# S7G7_footprint_simplified_w_ethernet_v1p.net
KiCad netlist of a schematic drawn in EAGLE
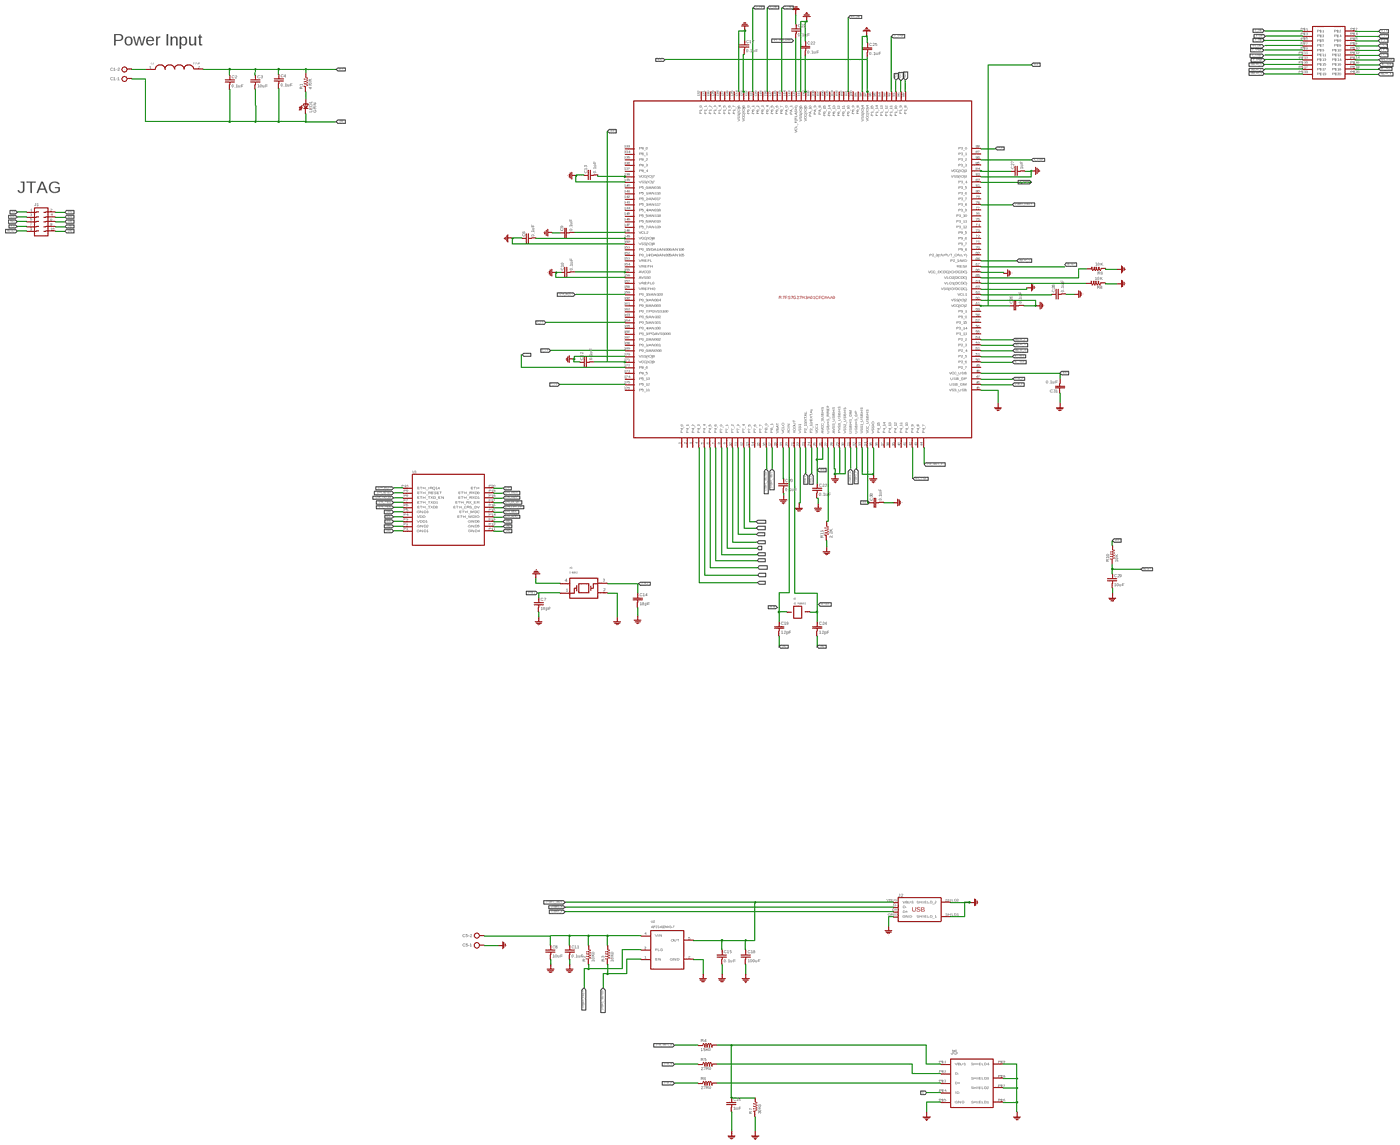
[diagram p0: schematic, sheet 1, overview]
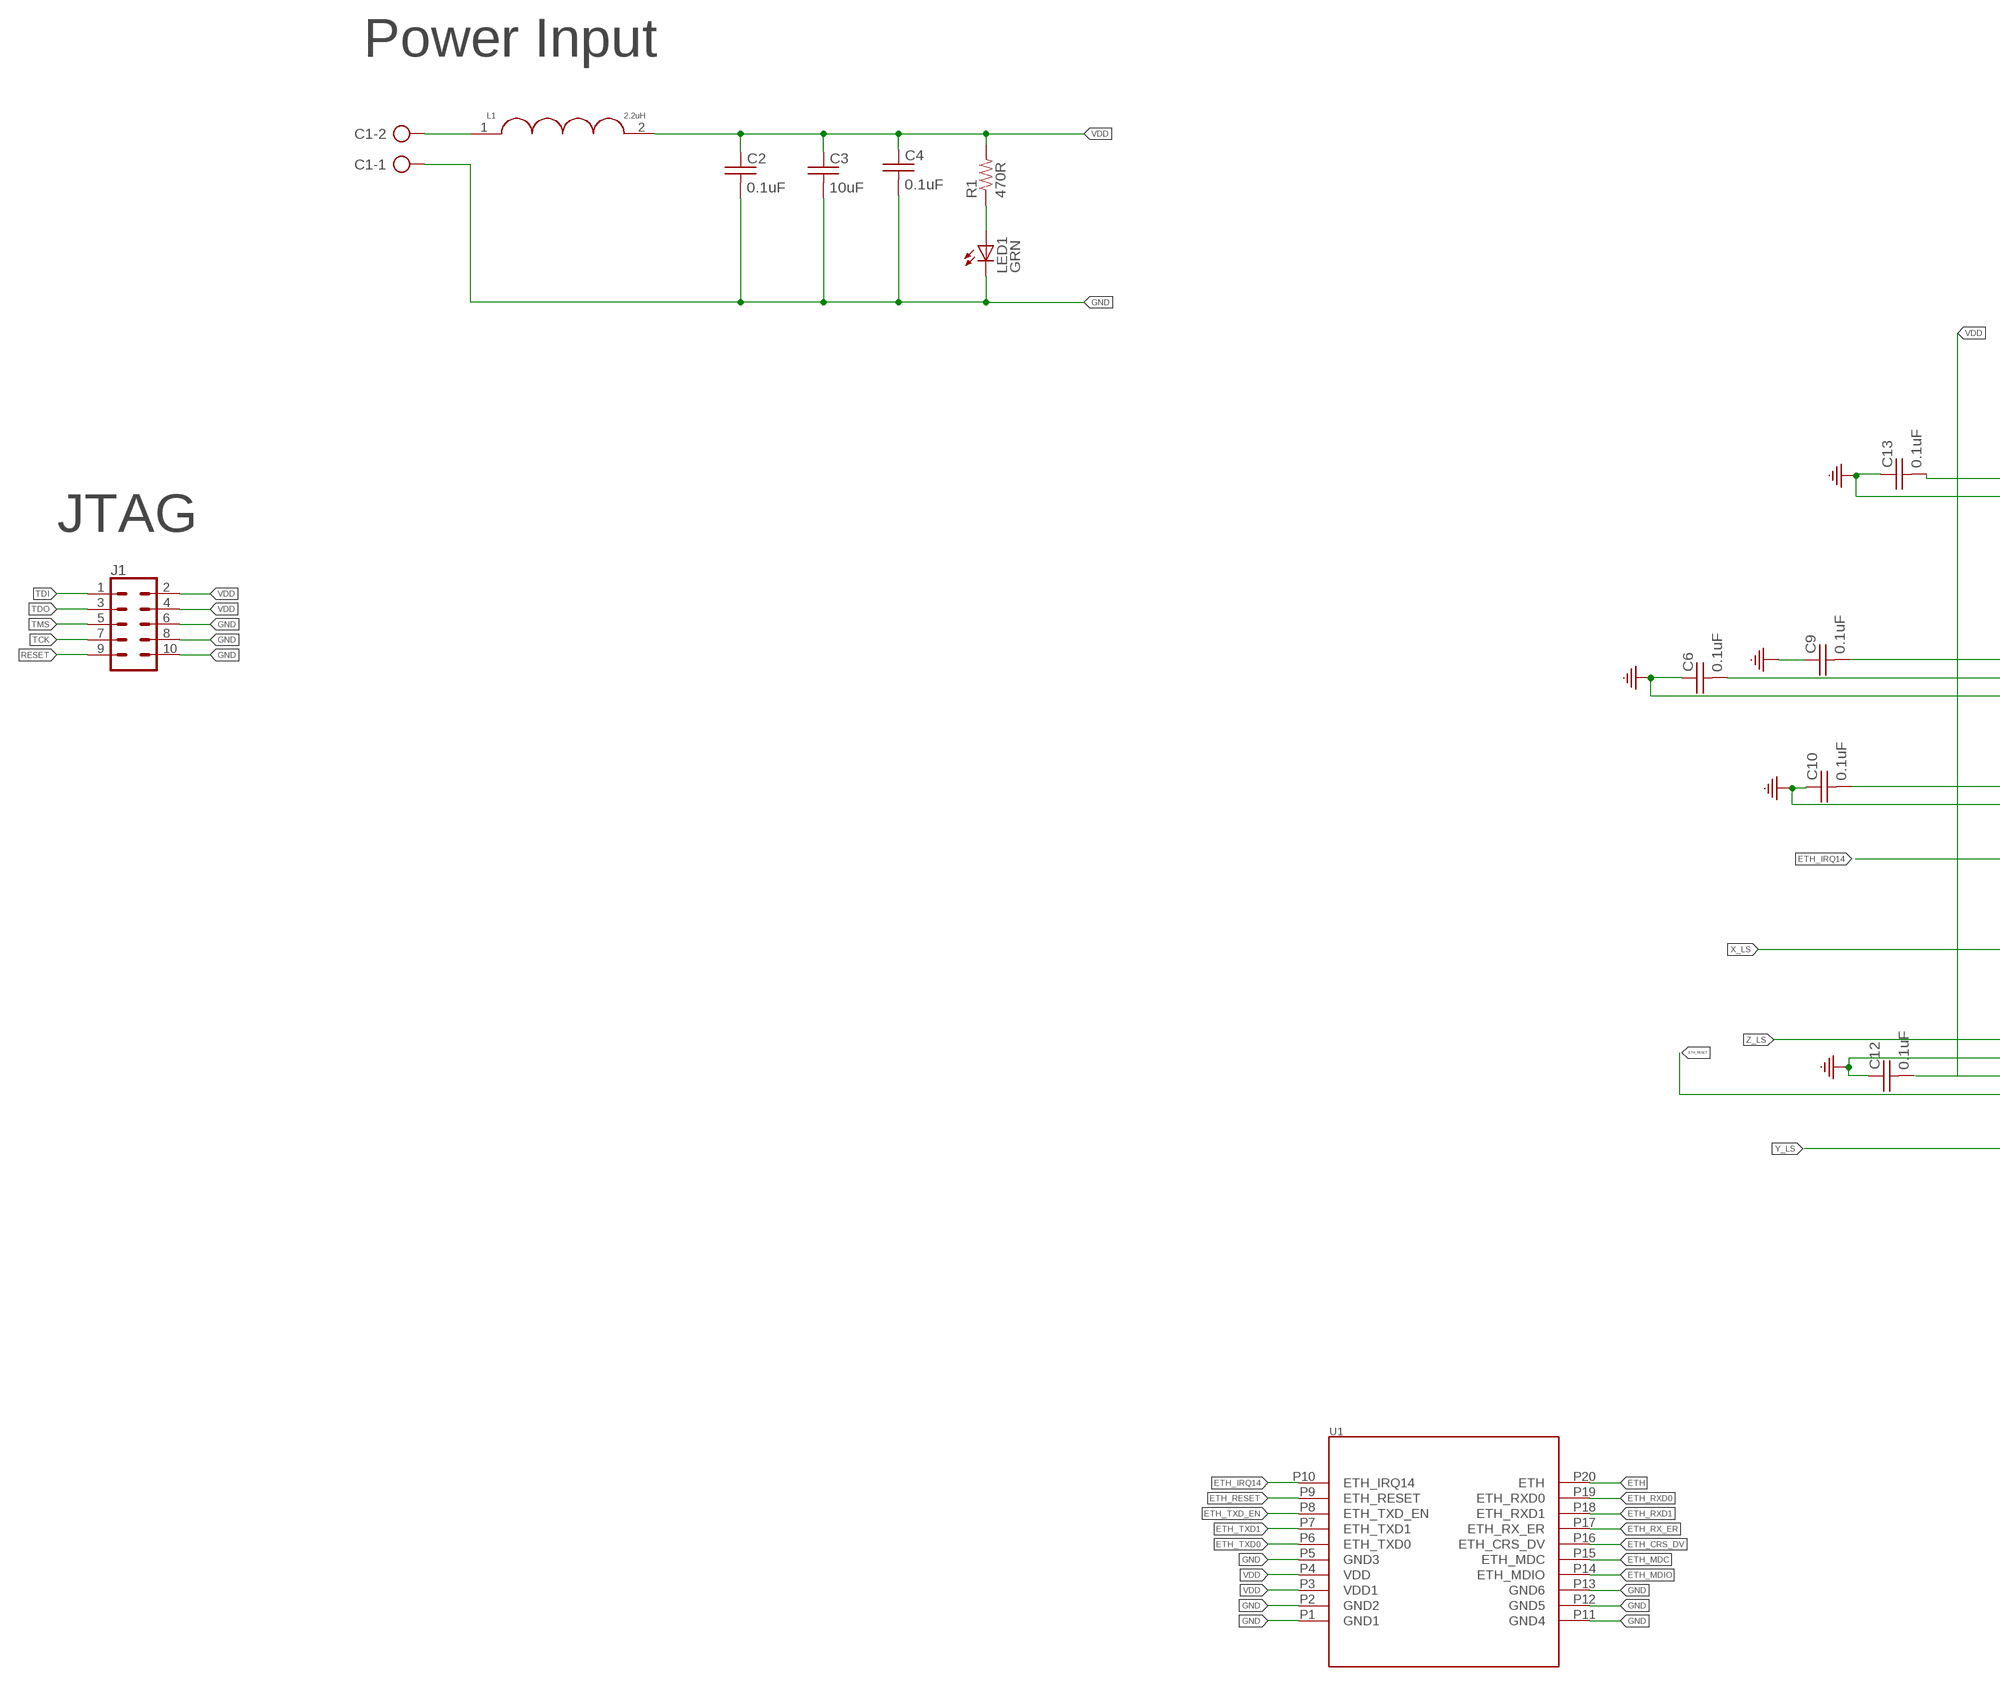
[diagram p1: schematic, sheet 1, part 1 of 4]
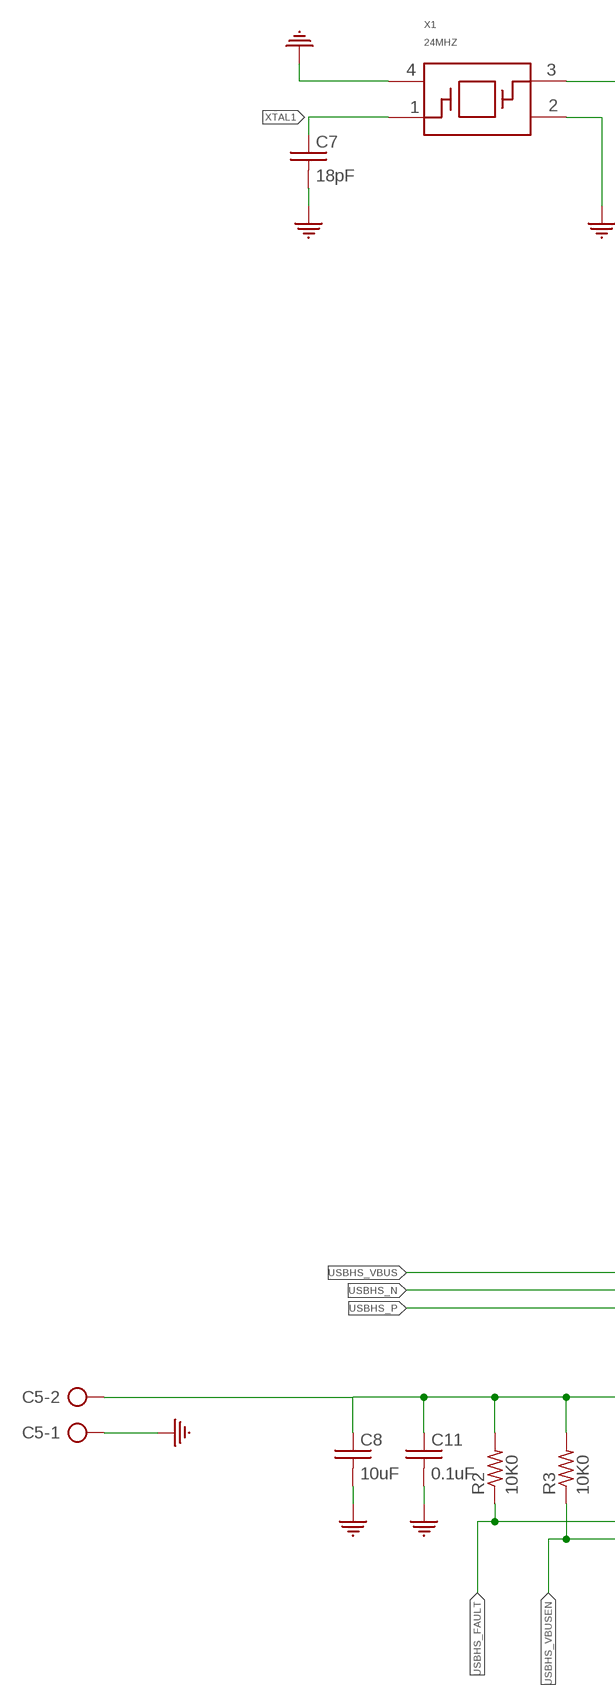
[diagram p2: schematic, sheet 1, part 2 of 4]
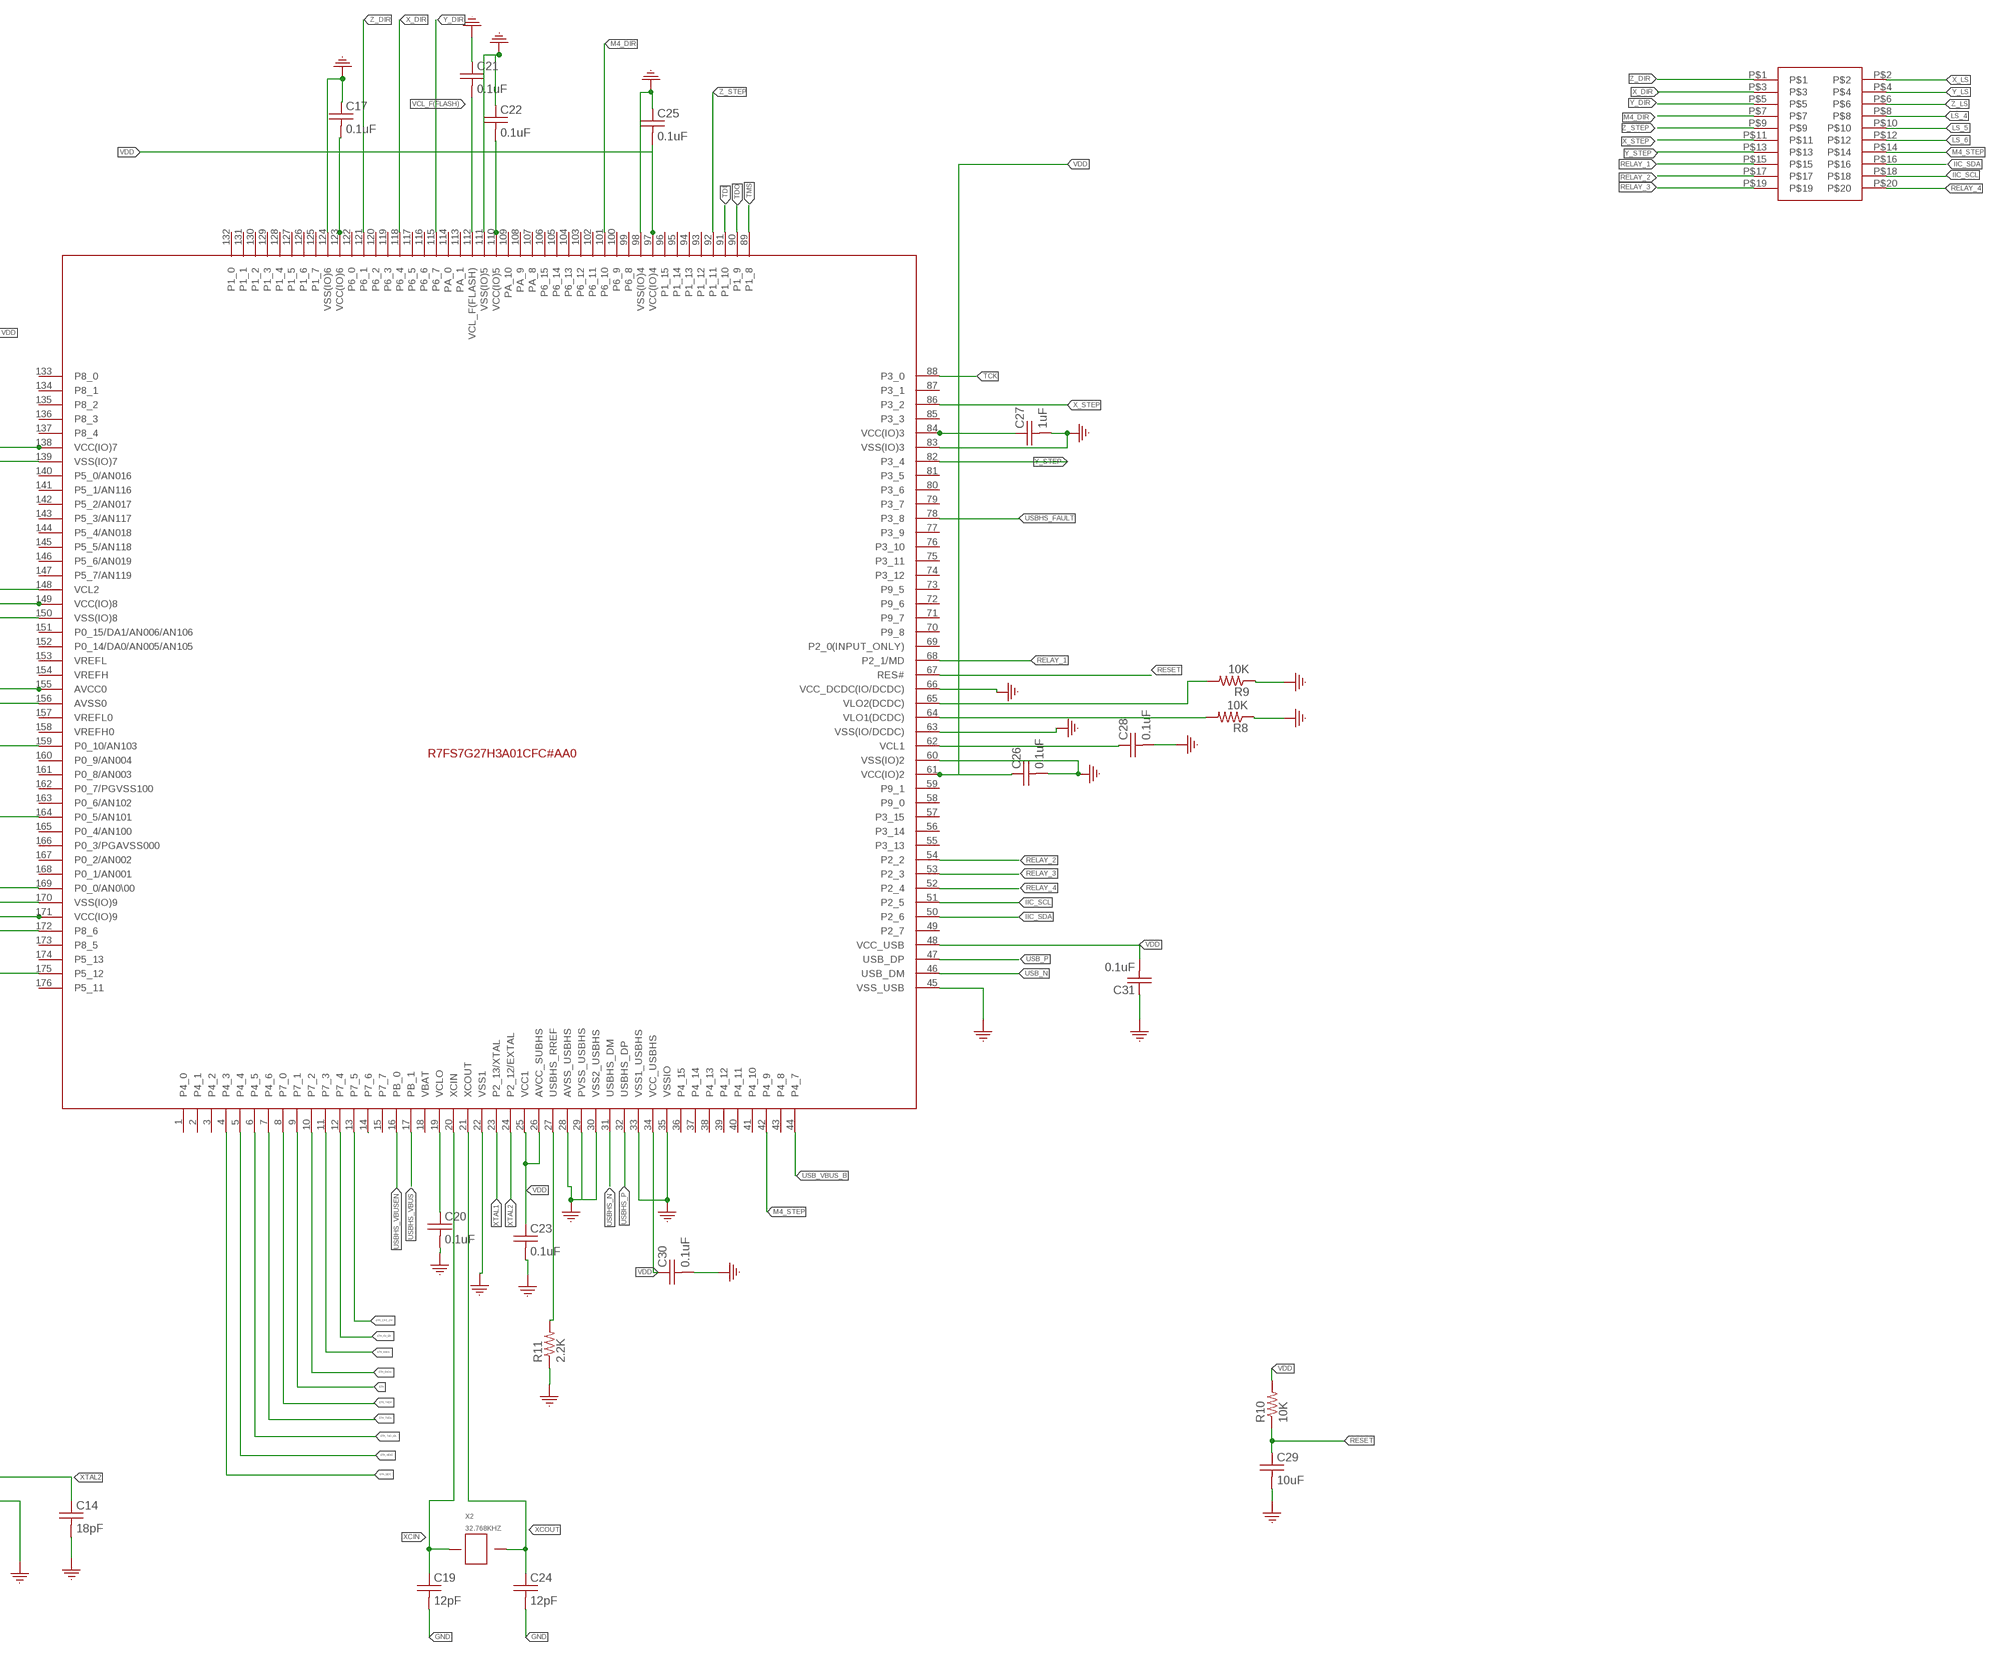
[diagram p3: schematic, sheet 1, part 3 of 4]
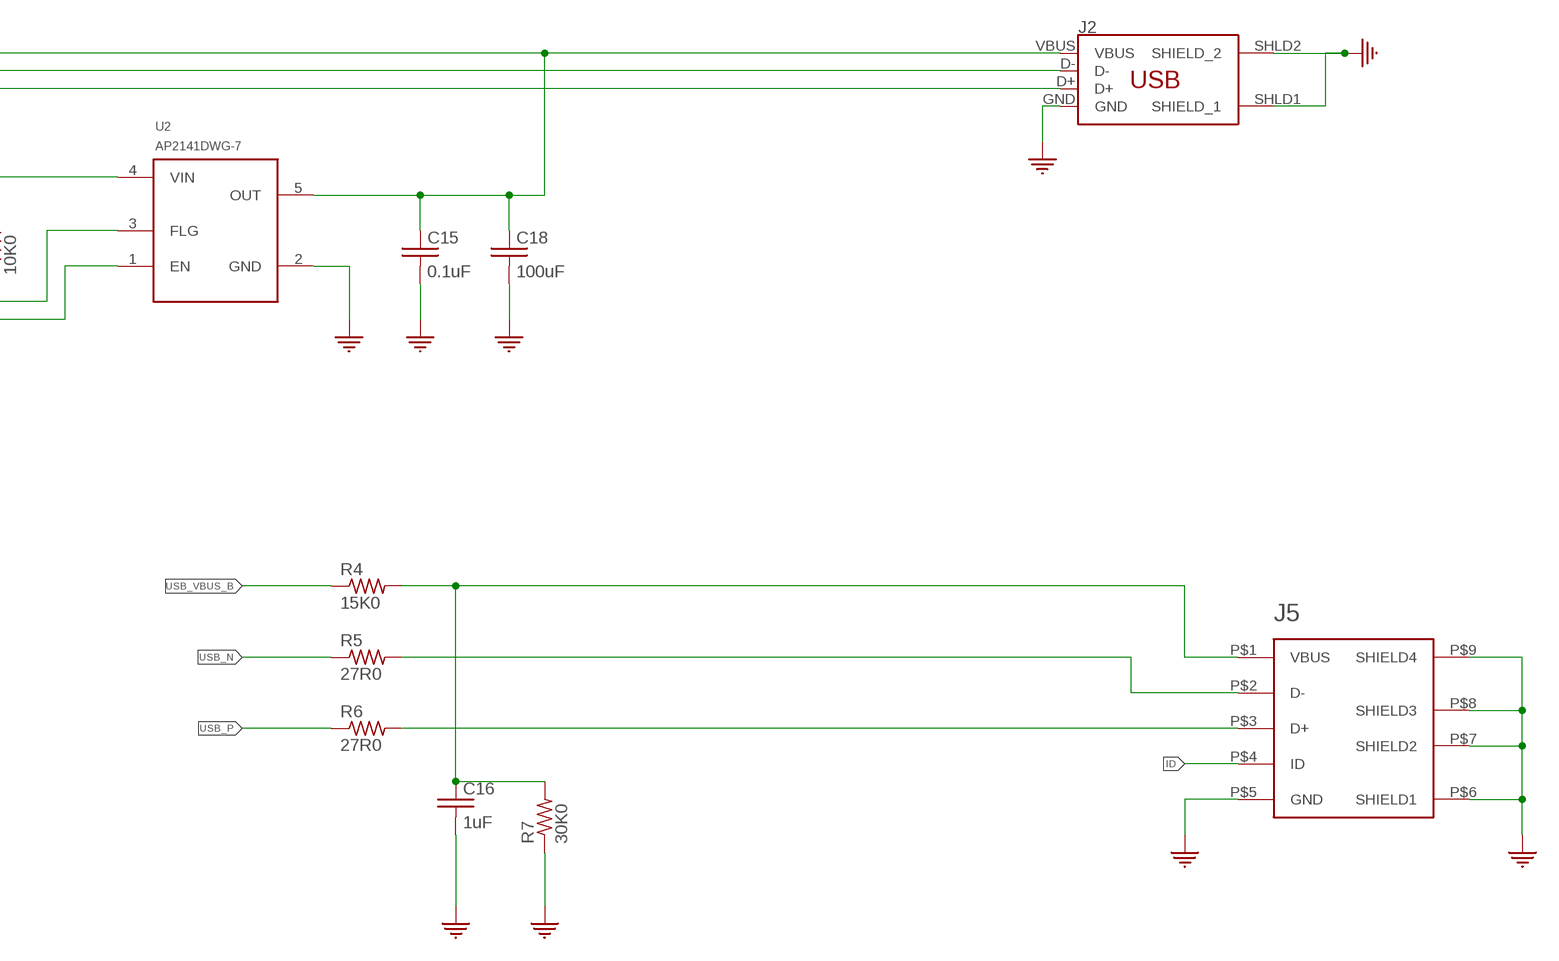
[diagram p4: schematic, sheet 1, part 4 of 4]

(export (version "E")
  (design (tool "Eeschema 10.0.6"))
  (components
    (comp (ref "C1")
      (value "AK300/2")
      (footprint "eagle-import:AK300_2")
      (libsource (lib "eagle-import") (part "AK300/2"))
    )
    (comp (ref "C2")
      (value "0.1uF")
      (footprint "eagle-import:0402")
      (libsource (lib "eagle-import") (part "C_0402"))
    )
    (comp (ref "C3")
      (value "10uF")
      (footprint "eagle-import:0402")
      (libsource (lib "eagle-import") (part "C_0402"))
    )
    (comp (ref "C4")
      (value "0.1uF")
      (footprint "eagle-import:0402")
      (libsource (lib "eagle-import") (part "C_0402"))
    )
    (comp (ref "C5")
      (value "AK300/2")
      (footprint "eagle-import:AK300_2")
      (libsource (lib "eagle-import") (part "AK300/2"))
    )
    (comp (ref "C6")
      (value "0.1uF")
      (footprint "eagle-import:0402")
      (libsource (lib "eagle-import") (part "C_0402"))
    )
    (comp (ref "C7")
      (value "18pF")
      (footprint "eagle-import:0402")
      (libsource (lib "eagle-import") (part "C_0402"))
    )
    (comp (ref "C8")
      (value "10uF")
      (footprint "eagle-import:0402")
      (libsource (lib "eagle-import") (part "C_0402"))
    )
    (comp (ref "C9")
      (value "0.1uF")
      (footprint "eagle-import:0402")
      (libsource (lib "eagle-import") (part "C_0402"))
    )
    (comp (ref "C10")
      (value "0.1uF")
      (footprint "eagle-import:0402")
      (libsource (lib "eagle-import") (part "C_0402"))
    )
    (comp (ref "C11")
      (value "0.1uF")
      (footprint "eagle-import:0402")
      (libsource (lib "eagle-import") (part "C_0402"))
    )
    (comp (ref "C12")
      (value "0.1uF")
      (footprint "eagle-import:0402")
      (libsource (lib "eagle-import") (part "C_0402"))
    )
    (comp (ref "C13")
      (value "0.1uF")
      (footprint "eagle-import:0402")
      (libsource (lib "eagle-import") (part "C_0402"))
    )
    (comp (ref "C14")
      (value "18pF")
      (footprint "eagle-import:0402")
      (libsource (lib "eagle-import") (part "C_0402"))
    )
    (comp (ref "C15")
      (value "0.1uF")
      (footprint "eagle-import:0402")
      (libsource (lib "eagle-import") (part "C_0402"))
    )
    (comp (ref "C16")
      (value "1uF")
      (footprint "eagle-import:0402")
      (libsource (lib "eagle-import") (part "C_0402"))
    )
    (comp (ref "C17")
      (value "0.1uF")
      (footprint "eagle-import:0402")
      (libsource (lib "eagle-import") (part "C_0402"))
    )
    (comp (ref "C18")
      (value "100uF")
      (footprint "eagle-import:C2917")
      (libsource (lib "eagle-import") (part "C_2917"))
    )
    (comp (ref "C19")
      (value "12pF")
      (footprint "eagle-import:0402")
      (libsource (lib "eagle-import") (part "C_0402"))
    )
    (comp (ref "C20")
      (value "0.1uF")
      (footprint "eagle-import:0402")
      (libsource (lib "eagle-import") (part "C_0402"))
    )
    (comp (ref "C21")
      (value "0.1uF")
      (footprint "eagle-import:0402")
      (libsource (lib "eagle-import") (part "C_0402"))
    )
    (comp (ref "C22")
      (value "0.1uF")
      (footprint "eagle-import:0402")
      (libsource (lib "eagle-import") (part "C_0402"))
    )
    (comp (ref "C23")
      (value "0.1uF")
      (footprint "eagle-import:0402")
      (libsource (lib "eagle-import") (part "C_0402"))
    )
    (comp (ref "C24")
      (value "12pF")
      (footprint "eagle-import:0402")
      (libsource (lib "eagle-import") (part "C_0402"))
    )
    (comp (ref "C25")
      (value "0.1uF")
      (footprint "eagle-import:0402")
      (libsource (lib "eagle-import") (part "C_0402"))
    )
    (comp (ref "C26")
      (value "0.1uF")
      (footprint "eagle-import:0402")
      (libsource (lib "eagle-import") (part "C_0402"))
    )
    (comp (ref "C27")
      (value "1uF")
      (footprint "eagle-import:0402")
      (libsource (lib "eagle-import") (part "C_0402"))
    )
    (comp (ref "C28")
      (value "0.1uF")
      (footprint "eagle-import:0402")
      (libsource (lib "eagle-import") (part "C_0402"))
    )
    (comp (ref "C29")
      (value "10uF")
      (footprint "eagle-import:0402")
      (libsource (lib "eagle-import") (part "C_0402"))
    )
    (comp (ref "C30")
      (value "0.1uF")
      (footprint "eagle-import:0402")
      (libsource (lib "eagle-import") (part "C_0402"))
    )
    (comp (ref "C31")
      (value "0.1uF")
      (footprint "eagle-import:0402")
      (libsource (lib "eagle-import") (part "C_0402"))
    )
    (comp (ref "J1")
      (value "CONN_05X2PTH")
      (footprint "eagle-import:2X5")
      (libsource (lib "eagle-import") (part "CONN_05X2PTH"))
    )
    (comp (ref "J2")
      (value "USB_A")
      (footprint "eagle-import:USB_A_SMT")
      (libsource (lib "eagle-import") (part "USB_A"))
    )
    (comp (ref "J4")
      (value "2_X_10_HEADER_GENERIC")
      (footprint "eagle-import:2_X_10_.1_INCH")
      (libsource (lib "eagle-import") (part "2_X_10_HEADER_GENERIC"))
    )
    (comp (ref "J5")
      (value "USB_MICRO-B")
      (footprint "eagle-import:USB_MICRO-B")
      (libsource (lib "eagle-import") (part "USB_MICRO-B"))
    )
    (comp (ref "L1")
      (value "2.2uH")
      (footprint "eagle-import:1008_(2520_METRIC)")
      (libsource (lib "eagle-import") (part "INDUCTOR_1008_2.2_MH_1.3A"))
    )
    (comp (ref "LED1")
      (value "LED_0805_GREEN")
      (footprint "eagle-import:LED_0805_GREEN")
      (libsource (lib "eagle-import") (part "LED_0805_GREEN"))
    )
    (comp (ref "R1")
      (value "470R")
      (footprint "eagle-import:0402")
      (libsource (lib "eagle-import") (part "R_0402"))
    )
    (comp (ref "R2")
      (value "10K0")
      (footprint "eagle-import:0402")
      (libsource (lib "eagle-import") (part "R_0402"))
    )
    (comp (ref "R3")
      (value "10K0")
      (footprint "eagle-import:0402")
      (libsource (lib "eagle-import") (part "R_0402"))
    )
    (comp (ref "R4")
      (value "15K0")
      (footprint "eagle-import:0402")
      (libsource (lib "eagle-import") (part "R_0402"))
    )
    (comp (ref "R5")
      (value "27R0")
      (footprint "eagle-import:0402")
      (libsource (lib "eagle-import") (part "R_0402"))
    )
    (comp (ref "R6")
      (value "27R0")
      (footprint "eagle-import:0402")
      (libsource (lib "eagle-import") (part "R_0402"))
    )
    (comp (ref "R7")
      (value "30K0")
      (footprint "eagle-import:0402")
      (libsource (lib "eagle-import") (part "R_0402"))
    )
    (comp (ref "R8")
      (value "10K")
      (footprint "eagle-import:0402")
      (libsource (lib "eagle-import") (part "R_0402"))
    )
    (comp (ref "R9")
      (value "10K")
      (footprint "eagle-import:0402")
      (libsource (lib "eagle-import") (part "R_0402"))
    )
    (comp (ref "R10")
      (value "10K")
      (footprint "eagle-import:0402")
      (libsource (lib "eagle-import") (part "R_0402"))
    )
    (comp (ref "R11")
      (value "2.2K")
      (footprint "eagle-import:0402")
      (libsource (lib "eagle-import") (part "R_0402"))
    )
    (comp (ref "U1")
      (value "ETHERNET_HAT")
      (footprint "eagle-import:ETHERNET_HAT")
      (libsource (lib "eagle-import") (part "ETHERNET_HAT"))
    )
    (comp (ref "U2")
      (value "AP2141DWG-5")
      (footprint "eagle-import:SOT-23-5")
      (libsource (lib "eagle-import") (part "AP2141DWG-5"))
    )
    (comp (ref "U5")
      (value "S7G2_X_176")
      (footprint "eagle-import:LQFP176_24X24")
      (libsource (lib "eagle-import") (part "S7G2_X_176"))
    )
    (comp (ref "X1")
      (value "24MHZ")
      (footprint "eagle-import:SMD_3225")
      (libsource (lib "eagle-import") (part "XTAL_24_MHZ"))
    )
    (comp (ref "X2")
      (value "32.768KHZ")
      (footprint "eagle-import:SMD_X_2_PADS")
      (libsource (lib "eagle-import") (part "XTAL_32.768KHZ"))
    )
  )
  (nets
    (net (code "1") (name "ETH") (class "Default")
      (node (ref "U1") (pin "P20") (pinfunction "ETH_P20") (pintype "bidirectional"))
      (node (ref "U5") (pin "9") (pinfunction "P7_1_9") (pintype "bidirectional"))
    )
    (net (code "2") (name "ETH_CRS_DV") (class "Default")
      (node (ref "U1") (pin "P16") (pinfunction "ETH_CRS_DV_P16") (pintype "bidirectional"))
      (node (ref "U5") (pin "13") (pinfunction "P7_5_13") (pintype "bidirectional"))
    )
    (net (code "3") (name "ETH_IRQ14") (class "Default")
      (node (ref "U1") (pin "P10") (pinfunction "ETH_IRQ14_P10") (pintype "bidirectional"))
      (node (ref "U5") (pin "159") (pinfunction "P0_10/AN103_159") (pintype "bidirectional"))
    )
    (net (code "4") (name "ETH_MDC") (class "Default")
      (node (ref "U1") (pin "P15") (pinfunction "ETH_MDC_P15") (pintype "bidirectional"))
      (node (ref "U5") (pin "4") (pinfunction "P4_3_4") (pintype "bidirectional"))
    )
    (net (code "5") (name "ETH_MDIO") (class "Default")
      (node (ref "U1") (pin "P14") (pinfunction "ETH_MDIO_P14") (pintype "bidirectional"))
      (node (ref "U5") (pin "5") (pinfunction "P4_4_5") (pintype "bidirectional"))
    )
    (net (code "6") (name "ETH_RESET") (class "Default")
      (node (ref "U1") (pin "P9") (pinfunction "ETH_RESET_P9") (pintype "bidirectional"))
      (node (ref "U5") (pin "172") (pinfunction "P8_6_172") (pintype "bidirectional"))
    )
    (net (code "7") (name "ETH_RXD0") (class "Default")
      (node (ref "U1") (pin "P19") (pinfunction "ETH_RXD0_P19") (pintype "bidirectional"))
      (node (ref "U5") (pin "10") (pinfunction "P7_2_10") (pintype "bidirectional"))
    )
    (net (code "8") (name "ETH_RXD1") (class "Default")
      (node (ref "U1") (pin "P18") (pinfunction "ETH_RXD1_P18") (pintype "bidirectional"))
      (node (ref "U5") (pin "11") (pinfunction "P7_3_11") (pintype "bidirectional"))
    )
    (net (code "9") (name "ETH_RX_ER") (class "Default")
      (node (ref "U1") (pin "P17") (pinfunction "ETH_RX_ER_P17") (pintype "bidirectional"))
      (node (ref "U5") (pin "12") (pinfunction "P7_4_12") (pintype "bidirectional"))
    )
    (net (code "10") (name "ETH_TXD0") (class "Default")
      (node (ref "U1") (pin "P6") (pinfunction "ETH_TXD0_P6") (pintype "bidirectional"))
      (node (ref "U5") (pin "8") (pinfunction "P7_0_8") (pintype "bidirectional"))
    )
    (net (code "11") (name "ETH_TXD1") (class "Default")
      (node (ref "U1") (pin "P7") (pinfunction "ETH_TXD1_P7") (pintype "bidirectional"))
      (node (ref "U5") (pin "7") (pinfunction "P4_6_7") (pintype "bidirectional"))
    )
    (net (code "12") (name "ETH_TXD_EN") (class "Default")
      (node (ref "U1") (pin "P8") (pinfunction "ETH_TXD_EN_P8") (pintype "bidirectional"))
      (node (ref "U5") (pin "6") (pinfunction "P4_5_6") (pintype "bidirectional"))
    )
    (net (code "13") (name "GND") (class "Default")
      (node (ref "C1") (pin "1") (pinfunction "KL_1") (pintype "passive"))
      (node (ref "C10") (pin "P$1") (pinfunction "1_P$1") (pintype "passive"))
      (node (ref "C11") (pin "P$2") (pinfunction "2_P$2") (pintype "passive"))
      (node (ref "C12") (pin "P$1") (pinfunction "1_P$1") (pintype "passive"))
      (node (ref "C13") (pin "P$1") (pinfunction "1_P$1") (pintype "passive"))
      (node (ref "C14") (pin "P$2") (pinfunction "2_P$2") (pintype "passive"))
      (node (ref "C15") (pin "P$2") (pinfunction "2_P$2") (pintype "passive"))
      (node (ref "C16") (pin "P$2") (pinfunction "2_P$2") (pintype "passive"))
      (node (ref "C17") (pin "P$1") (pinfunction "1_P$1") (pintype "passive"))
      (node (ref "C18") (pin "2") (pinfunction "2_2") (pintype "passive"))
      (node (ref "C19") (pin "P$2") (pinfunction "2_P$2") (pintype "passive"))
      (node (ref "C2") (pin "P$2") (pinfunction "2_P$2") (pintype "passive"))
      (node (ref "C20") (pin "P$2") (pinfunction "2_P$2") (pintype "passive"))
      (node (ref "C21") (pin "P$1") (pinfunction "1_P$1") (pintype "passive"))
      (node (ref "C22") (pin "P$1") (pinfunction "1_P$1") (pintype "passive"))
      (node (ref "C23") (pin "P$2") (pinfunction "2_P$2") (pintype "passive"))
      (node (ref "C24") (pin "P$2") (pinfunction "2_P$2") (pintype "passive"))
      (node (ref "C25") (pin "P$1") (pinfunction "1_P$1") (pintype "passive"))
      (node (ref "C26") (pin "P$2") (pinfunction "2_P$2") (pintype "passive"))
      (node (ref "C27") (pin "P$2") (pinfunction "2_P$2") (pintype "passive"))
      (node (ref "C28") (pin "P$2") (pinfunction "2_P$2") (pintype "passive"))
      (node (ref "C29") (pin "P$2") (pinfunction "2_P$2") (pintype "passive"))
      (node (ref "C3") (pin "P$2") (pinfunction "2_P$2") (pintype "passive"))
      (node (ref "C30") (pin "P$2") (pinfunction "2_P$2") (pintype "passive"))
      (node (ref "C31") (pin "P$1") (pinfunction "1_P$1") (pintype "passive"))
      (node (ref "C4") (pin "P$2") (pinfunction "2_P$2") (pintype "passive"))
      (node (ref "C5") (pin "1") (pinfunction "KL_1") (pintype "passive"))
      (node (ref "C6") (pin "P$1") (pinfunction "1_P$1") (pintype "passive"))
      (node (ref "C7") (pin "P$2") (pinfunction "2_P$2") (pintype "passive"))
      (node (ref "C8") (pin "P$2") (pinfunction "2_P$2") (pintype "passive"))
      (node (ref "C9") (pin "P$1") (pinfunction "1_P$1") (pintype "passive"))
      (node (ref "J1") (pin "10") (pinfunction "10_10") (pintype "passive"))
      (node (ref "J1") (pin "6") (pinfunction "6_6") (pintype "passive"))
      (node (ref "J1") (pin "8") (pinfunction "8_8") (pintype "passive"))
      (node (ref "J2") (pin "GND") (pinfunction "GND_GND") (pintype "power_in"))
      (node (ref "J2") (pin "SHLD1") (pinfunction "SHIELD_1_SHLD1") (pintype "bidirectional"))
      (node (ref "J2") (pin "SHLD2") (pinfunction "SHIELD_2_SHLD2") (pintype "bidirectional"))
      (node (ref "J5") (pin "P$5") (pinfunction "GND_P$5") (pintype "bidirectional"))
      (node (ref "J5") (pin "P$6") (pinfunction "SHIELD1_P$6") (pintype "bidirectional"))
      (node (ref "J5") (pin "P$7") (pinfunction "SHIELD2_P$7") (pintype "bidirectional"))
      (node (ref "J5") (pin "P$8") (pinfunction "SHIELD3_P$8") (pintype "bidirectional"))
      (node (ref "J5") (pin "P$9") (pinfunction "SHIELD4_P$9") (pintype "bidirectional"))
      (node (ref "LED1") (pin "C") (pinfunction "C_C") (pintype "passive"))
      (node (ref "R11") (pin "P$1") (pinfunction "1_P$1") (pintype "passive"))
      (node (ref "R7") (pin "P$1") (pinfunction "1_P$1") (pintype "passive"))
      (node (ref "R8") (pin "P$1") (pinfunction "1_P$1") (pintype "passive"))
      (node (ref "R9") (pin "P$1") (pinfunction "1_P$1") (pintype "passive"))
      (node (ref "U1") (pin "P1") (pinfunction "GND1_P1") (pintype "bidirectional"))
      (node (ref "U1") (pin "P11") (pinfunction "GND4_P11") (pintype "bidirectional"))
      (node (ref "U1") (pin "P12") (pinfunction "GND5_P12") (pintype "bidirectional"))
      (node (ref "U1") (pin "P13") (pinfunction "GND6_P13") (pintype "bidirectional"))
      (node (ref "U1") (pin "P2") (pinfunction "GND2_P2") (pintype "bidirectional"))
      (node (ref "U1") (pin "P5") (pinfunction "GND3_P5") (pintype "bidirectional"))
      (node (ref "U2") (pin "2") (pinfunction "GND_2") (pintype "input"))
      (node (ref "U5") (pin "111") (pinfunction "VSS(IO)5_111") (pintype "bidirectional"))
      (node (ref "U5") (pin "124") (pinfunction "VSS(IO)6_124") (pintype "bidirectional"))
      (node (ref "U5") (pin "139") (pinfunction "VSS(IO)7_139") (pintype "bidirectional"))
      (node (ref "U5") (pin "150") (pinfunction "VSS(IO)8_150") (pintype "bidirectional"))
      (node (ref "U5") (pin "156") (pinfunction "AVSS0_156") (pintype "bidirectional"))
      (node (ref "U5") (pin "170") (pinfunction "VSS(IO)9_170") (pintype "bidirectional"))
      (node (ref "U5") (pin "22") (pinfunction "VSS1_22") (pintype "bidirectional"))
      (node (ref "U5") (pin "28") (pinfunction "AVSS_USBHS_28") (pintype "bidirectional"))
      (node (ref "U5") (pin "29") (pinfunction "PVSS_USBHS_29") (pintype "bidirectional"))
      (node (ref "U5") (pin "30") (pinfunction "VSS2_USBHS_30") (pintype "bidirectional"))
      (node (ref "U5") (pin "33") (pinfunction "VSS1_USBHS_33") (pintype "bidirectional"))
      (node (ref "U5") (pin "35") (pinfunction "VSSIO_35") (pintype "bidirectional"))
      (node (ref "U5") (pin "45") (pinfunction "VSS_USB_45") (pintype "bidirectional"))
      (node (ref "U5") (pin "60") (pinfunction "VSS(IO)2_60") (pintype "bidirectional"))
      (node (ref "U5") (pin "63") (pinfunction "VSS(IO/DCDC)_63") (pintype "bidirectional"))
      (node (ref "U5") (pin "66") (pinfunction "VCC_DCDC(IO/DCDC)_66") (pintype "bidirectional"))
      (node (ref "U5") (pin "83") (pinfunction "VSS(IO)3_83") (pintype "bidirectional"))
      (node (ref "U5") (pin "98") (pinfunction "VSS(IO)4_98") (pintype "bidirectional"))
      (node (ref "X1") (pin "2") (pinfunction "2_2") (pintype "bidirectional"))
      (node (ref "X1") (pin "4") (pinfunction "4_4") (pintype "bidirectional"))
    )
    (net (code "14") (name "ID") (class "Default")
      (node (ref "J5") (pin "P$4") (pinfunction "ID_P$4") (pintype "bidirectional"))
    )
    (net (code "15") (name "IIC_SCL") (class "Default")
      (node (ref "J4") (pin "P$18") (pinfunction "P$18_P$18") (pintype "bidirectional"))
      (node (ref "U5") (pin "51") (pinfunction "P2_5_51") (pintype "bidirectional"))
    )
    (net (code "16") (name "IIC_SDA") (class "Default")
      (node (ref "J4") (pin "P$16") (pinfunction "P$16_P$16") (pintype "bidirectional"))
      (node (ref "U5") (pin "50") (pinfunction "P2_6_50") (pintype "bidirectional"))
    )
    (net (code "17") (name "LS_4") (class "Default")
      (node (ref "J4") (pin "P$8") (pinfunction "P$8_P$8") (pintype "bidirectional"))
    )
    (net (code "18") (name "LS_5") (class "Default")
      (node (ref "J4") (pin "P$10") (pinfunction "P$10_P$10") (pintype "bidirectional"))
    )
    (net (code "19") (name "LS_6") (class "Default")
      (node (ref "J4") (pin "P$12") (pinfunction "P$12_P$12") (pintype "bidirectional"))
    )
    (net (code "20") (name "M4_DIR") (class "Default")
      (node (ref "J4") (pin "P$7") (pinfunction "P$7_P$7") (pintype "bidirectional"))
      (node (ref "U5") (pin "101") (pinfunction "P6_10_101") (pintype "bidirectional"))
    )
    (net (code "21") (name "M4_STEP") (class "Default")
      (node (ref "J4") (pin "P$14") (pinfunction "P$14_P$14") (pintype "bidirectional"))
      (node (ref "U5") (pin "42") (pinfunction "P4_9_42") (pintype "bidirectional"))
    )
    (net (code "22") (name "Net-(C1B-KL)") (class "Default")
      (node (ref "C1") (pin "2") (pinfunction "KL_2") (pintype "passive"))
      (node (ref "L1") (pin "1") (pinfunction "P$1_1") (pintype "bidirectional"))
    )
    (net (code "23") (name "Net-(C9-2)") (class "Default")
      (node (ref "C9") (pin "P$2") (pinfunction "2_P$2") (pintype "passive"))
      (node (ref "U5") (pin "148") (pinfunction "VCL2_148") (pintype "bidirectional"))
    )
    (net (code "24") (name "Net-(C11-1)") (class "Default")
      (node (ref "C11") (pin "P$1") (pinfunction "1_P$1") (pintype "passive"))
      (node (ref "C5") (pin "2") (pinfunction "KL_2") (pintype "passive"))
      (node (ref "C8") (pin "P$1") (pinfunction "1_P$1") (pintype "passive"))
      (node (ref "R2") (pin "P$2") (pinfunction "2_P$2") (pintype "passive"))
      (node (ref "R3") (pin "P$2") (pinfunction "2_P$2") (pintype "passive"))
      (node (ref "U2") (pin "4") (pinfunction "VIN_4") (pintype "input"))
    )
    (net (code "25") (name "Net-(C16-1)") (class "Default")
      (node (ref "C16") (pin "P$1") (pinfunction "1_P$1") (pintype "passive"))
      (node (ref "J5") (pin "P$1") (pinfunction "VBUS_P$1") (pintype "bidirectional"))
      (node (ref "R4") (pin "P$2") (pinfunction "2_P$2") (pintype "passive"))
      (node (ref "R7") (pin "P$2") (pinfunction "2_P$2") (pintype "passive"))
    )
    (net (code "26") (name "Net-(C20-1)") (class "Default")
      (node (ref "C20") (pin "P$1") (pinfunction "1_P$1") (pintype "passive"))
      (node (ref "U5") (pin "19") (pinfunction "VCLO_19") (pintype "bidirectional"))
    )
    (net (code "27") (name "Net-(C28-1)") (class "Default")
      (node (ref "C28") (pin "P$1") (pinfunction "1_P$1") (pintype "passive"))
      (node (ref "U5") (pin "62") (pinfunction "VCL1_62") (pintype "bidirectional"))
    )
    (net (code "28") (name "Net-(J5-D+)") (class "Default")
      (node (ref "J5") (pin "P$3") (pinfunction "D+_P$3") (pintype "bidirectional"))
      (node (ref "R6") (pin "P$2") (pinfunction "2_P$2") (pintype "passive"))
    )
    (net (code "29") (name "Net-(J5-D-)") (class "Default")
      (node (ref "J5") (pin "P$2") (pinfunction "D-_P$2") (pintype "bidirectional"))
      (node (ref "R5") (pin "P$2") (pinfunction "2_P$2") (pintype "passive"))
    )
    (net (code "30") (name "Net-(R1-1)") (class "Default")
      (node (ref "LED1") (pin "A") (pinfunction "A_A") (pintype "passive"))
      (node (ref "R1") (pin "P$1") (pinfunction "1_P$1") (pintype "passive"))
    )
    (net (code "31") (name "Net-(R8-2)") (class "Default")
      (node (ref "R8") (pin "P$2") (pinfunction "2_P$2") (pintype "passive"))
      (node (ref "U5") (pin "64") (pinfunction "VLO1(DCDC)_64") (pintype "bidirectional"))
    )
    (net (code "32") (name "Net-(R9-2)") (class "Default")
      (node (ref "R9") (pin "P$2") (pinfunction "2_P$2") (pintype "passive"))
      (node (ref "U5") (pin "65") (pinfunction "VLO2(DCDC)_65") (pintype "bidirectional"))
    )
    (net (code "33") (name "Net-(R11-2)") (class "Default")
      (node (ref "R11") (pin "P$2") (pinfunction "2_P$2") (pintype "passive"))
      (node (ref "U5") (pin "27") (pinfunction "USBHS_RREF_27") (pintype "bidirectional"))
    )
    (net (code "34") (name "RELAY_1") (class "Default")
      (node (ref "J4") (pin "P$15") (pinfunction "P$15_P$15") (pintype "bidirectional"))
      (node (ref "U5") (pin "68") (pinfunction "P2_1/MD_68") (pintype "bidirectional"))
    )
    (net (code "35") (name "RELAY_2") (class "Default")
      (node (ref "J4") (pin "P$17") (pinfunction "P$17_P$17") (pintype "bidirectional"))
      (node (ref "U5") (pin "54") (pinfunction "P2_2_54") (pintype "bidirectional"))
    )
    (net (code "36") (name "RELAY_3") (class "Default")
      (node (ref "J4") (pin "P$19") (pinfunction "P$19_P$19") (pintype "bidirectional"))
      (node (ref "U5") (pin "53") (pinfunction "P2_3_53") (pintype "bidirectional"))
    )
    (net (code "37") (name "RELAY_4") (class "Default")
      (node (ref "J4") (pin "P$20") (pinfunction "P$20_P$20") (pintype "bidirectional"))
      (node (ref "U5") (pin "52") (pinfunction "P2_4_52") (pintype "bidirectional"))
    )
    (net (code "38") (name "RESET") (class "Default")
      (node (ref "C29") (pin "P$1") (pinfunction "1_P$1") (pintype "passive"))
      (node (ref "J1") (pin "9") (pinfunction "9_9") (pintype "passive"))
      (node (ref "R10") (pin "P$1") (pinfunction "1_P$1") (pintype "passive"))
      (node (ref "U5") (pin "67") (pinfunction "RES#_67") (pintype "bidirectional"))
    )
    (net (code "39") (name "TCK") (class "Default")
      (node (ref "J1") (pin "7") (pinfunction "7_7") (pintype "passive"))
      (node (ref "U5") (pin "88") (pinfunction "P3_0_88") (pintype "bidirectional"))
    )
    (net (code "40") (name "TDI") (class "Default")
      (node (ref "J1") (pin "1") (pinfunction "1_1") (pintype "passive"))
      (node (ref "U5") (pin "91") (pinfunction "P1_10_91") (pintype "bidirectional"))
    )
    (net (code "41") (name "TDO") (class "Default")
      (node (ref "J1") (pin "3") (pinfunction "3_3") (pintype "passive"))
      (node (ref "U5") (pin "90") (pinfunction "P1_9_90") (pintype "bidirectional"))
    )
    (net (code "42") (name "TMS") (class "Default")
      (node (ref "J1") (pin "5") (pinfunction "5_5") (pintype "passive"))
      (node (ref "U5") (pin "89") (pinfunction "P1_8_89") (pintype "bidirectional"))
    )
    (net (code "43") (name "USBHS_FAULT") (class "Default")
      (node (ref "R2") (pin "P$1") (pinfunction "1_P$1") (pintype "passive"))
      (node (ref "U2") (pin "3") (pinfunction "FLG_3") (pintype "input"))
      (node (ref "U5") (pin "78") (pinfunction "P3_8_78") (pintype "bidirectional"))
    )
    (net (code "44") (name "USBHS_N") (class "Default")
      (node (ref "J2") (pin "D-") (pinfunction "D-_D-") (pintype "bidirectional"))
      (node (ref "U5") (pin "31") (pinfunction "USBHS_DM_31") (pintype "bidirectional"))
    )
    (net (code "45") (name "USBHS_P") (class "Default")
      (node (ref "J2") (pin "D+") (pinfunction "D+_D+") (pintype "bidirectional"))
      (node (ref "U5") (pin "32") (pinfunction "USBHS_DP_32") (pintype "bidirectional"))
    )
    (net (code "46") (name "USBHS_VBUS") (class "Default")
      (node (ref "C15") (pin "P$1") (pinfunction "1_P$1") (pintype "passive"))
      (node (ref "C18") (pin "1") (pinfunction "1_1") (pintype "passive"))
      (node (ref "J2") (pin "VBUS") (pinfunction "VBUS_VBUS") (pintype "power_in"))
      (node (ref "U2") (pin "5") (pinfunction "OUT_5") (pintype "input"))
      (node (ref "U5") (pin "17") (pinfunction "PB_1_17") (pintype "bidirectional"))
    )
    (net (code "47") (name "USBHS_VBUSEN") (class "Default")
      (node (ref "R3") (pin "P$1") (pinfunction "1_P$1") (pintype "passive"))
      (node (ref "U2") (pin "1") (pinfunction "EN_1") (pintype "input"))
      (node (ref "U5") (pin "16") (pinfunction "PB_0_16") (pintype "bidirectional"))
    )
    (net (code "48") (name "USB_N") (class "Default")
      (node (ref "R5") (pin "P$1") (pinfunction "1_P$1") (pintype "passive"))
      (node (ref "U5") (pin "46") (pinfunction "USB_DM_46") (pintype "bidirectional"))
    )
    (net (code "49") (name "USB_P") (class "Default")
      (node (ref "R6") (pin "P$1") (pinfunction "1_P$1") (pintype "passive"))
      (node (ref "U5") (pin "47") (pinfunction "USB_DP_47") (pintype "bidirectional"))
    )
    (net (code "50") (name "USB_VBUS_B") (class "Default")
      (node (ref "R4") (pin "P$1") (pinfunction "1_P$1") (pintype "passive"))
      (node (ref "U5") (pin "44") (pinfunction "P4_7_44") (pintype "bidirectional"))
    )
    (net (code "51") (name "VCL_F(FLASH)") (class "Default")
      (node (ref "C21") (pin "P$2") (pinfunction "2_P$2") (pintype "passive"))
      (node (ref "U5") (pin "112") (pinfunction "VCL_F(FLASH)_112") (pintype "bidirectional"))
    )
    (net (code "52") (name "VDD") (class "Default")
      (node (ref "C10") (pin "P$2") (pinfunction "2_P$2") (pintype "passive"))
      (node (ref "C12") (pin "P$2") (pinfunction "2_P$2") (pintype "passive"))
      (node (ref "C13") (pin "P$2") (pinfunction "2_P$2") (pintype "passive"))
      (node (ref "C17") (pin "P$2") (pinfunction "2_P$2") (pintype "passive"))
      (node (ref "C2") (pin "P$1") (pinfunction "1_P$1") (pintype "passive"))
      (node (ref "C22") (pin "P$2") (pinfunction "2_P$2") (pintype "passive"))
      (node (ref "C23") (pin "P$1") (pinfunction "1_P$1") (pintype "passive"))
      (node (ref "C25") (pin "P$2") (pinfunction "2_P$2") (pintype "passive"))
      (node (ref "C26") (pin "P$1") (pinfunction "1_P$1") (pintype "passive"))
      (node (ref "C27") (pin "P$1") (pinfunction "1_P$1") (pintype "passive"))
      (node (ref "C3") (pin "P$1") (pinfunction "1_P$1") (pintype "passive"))
      (node (ref "C30") (pin "P$1") (pinfunction "1_P$1") (pintype "passive"))
      (node (ref "C31") (pin "P$2") (pinfunction "2_P$2") (pintype "passive"))
      (node (ref "C4") (pin "P$1") (pinfunction "1_P$1") (pintype "passive"))
      (node (ref "C6") (pin "P$2") (pinfunction "2_P$2") (pintype "passive"))
      (node (ref "J1") (pin "2") (pinfunction "2_2") (pintype "passive"))
      (node (ref "J1") (pin "4") (pinfunction "4_4") (pintype "passive"))
      (node (ref "L1") (pin "2") (pinfunction "P$2_2") (pintype "bidirectional"))
      (node (ref "R1") (pin "P$2") (pinfunction "2_P$2") (pintype "passive"))
      (node (ref "R10") (pin "P$2") (pinfunction "2_P$2") (pintype "passive"))
      (node (ref "U1") (pin "P3") (pinfunction "VDD1_P3") (pintype "bidirectional"))
      (node (ref "U1") (pin "P4") (pinfunction "VDD_P4") (pintype "bidirectional"))
      (node (ref "U5") (pin "110") (pinfunction "VCC(IO)5_110") (pintype "bidirectional"))
      (node (ref "U5") (pin "123") (pinfunction "VCC(IO)6_123") (pintype "bidirectional"))
      (node (ref "U5") (pin "138") (pinfunction "VCC(IO)7_138") (pintype "bidirectional"))
      (node (ref "U5") (pin "149") (pinfunction "VCC(IO)8_149") (pintype "bidirectional"))
      (node (ref "U5") (pin "155") (pinfunction "AVCC0_155") (pintype "bidirectional"))
      (node (ref "U5") (pin "171") (pinfunction "VCC(IO)9_171") (pintype "bidirectional"))
      (node (ref "U5") (pin "25") (pinfunction "VCC1_25") (pintype "bidirectional"))
      (node (ref "U5") (pin "26") (pinfunction "AVCC_SUBHS_26") (pintype "bidirectional"))
      (node (ref "U5") (pin "34") (pinfunction "VCC_USBHS_34") (pintype "bidirectional"))
      (node (ref "U5") (pin "48") (pinfunction "VCC_USB_48") (pintype "bidirectional"))
      (node (ref "U5") (pin "61") (pinfunction "VCC(IO)2_61") (pintype "bidirectional"))
      (node (ref "U5") (pin "84") (pinfunction "VCC(IO)3_84") (pintype "bidirectional"))
      (node (ref "U5") (pin "97") (pinfunction "VCC(IO)4_97") (pintype "bidirectional"))
    )
    (net (code "53") (name "XCIN") (class "Default")
      (node (ref "C19") (pin "P$1") (pinfunction "1_P$1") (pintype "passive"))
      (node (ref "U5") (pin "20") (pinfunction "XCIN_20") (pintype "bidirectional"))
      (node (ref "X2") (pin "P$1") (pinfunction "P$1_P$1") (pintype "bidirectional"))
    )
    (net (code "54") (name "XCOUT") (class "Default")
      (node (ref "C24") (pin "P$1") (pinfunction "1_P$1") (pintype "passive"))
      (node (ref "U5") (pin "21") (pinfunction "XCOUT_21") (pintype "bidirectional"))
      (node (ref "X2") (pin "P$2") (pinfunction "P$2_P$2") (pintype "bidirectional"))
    )
    (net (code "55") (name "XTAL1") (class "Default")
      (node (ref "C7") (pin "P$1") (pinfunction "1_P$1") (pintype "passive"))
      (node (ref "U5") (pin "23") (pinfunction "P2_13/XTAL_23") (pintype "bidirectional"))
      (node (ref "X1") (pin "1") (pinfunction "1_1") (pintype "bidirectional"))
    )
    (net (code "56") (name "XTAL2") (class "Default")
      (node (ref "C14") (pin "P$1") (pinfunction "1_P$1") (pintype "passive"))
      (node (ref "U5") (pin "24") (pinfunction "P2_12/EXTAL_24") (pintype "bidirectional"))
      (node (ref "X1") (pin "3") (pinfunction "3_3") (pintype "bidirectional"))
    )
    (net (code "57") (name "X_DIR") (class "Default")
      (node (ref "J4") (pin "P$3") (pinfunction "P$3_P$3") (pintype "bidirectional"))
      (node (ref "U5") (pin "118") (pinfunction "P6_4_118") (pintype "bidirectional"))
    )
    (net (code "58") (name "X_LS") (class "Default")
      (node (ref "J4") (pin "P$2") (pinfunction "P$2_P$2") (pintype "bidirectional"))
      (node (ref "U5") (pin "164") (pinfunction "P0_5/AN101_164") (pintype "bidirectional"))
    )
    (net (code "59") (name "X_STEP") (class "Default")
      (node (ref "J4") (pin "P$11") (pinfunction "P$11_P$11") (pintype "bidirectional"))
      (node (ref "U5") (pin "86") (pinfunction "P3_2_86") (pintype "bidirectional"))
    )
    (net (code "60") (name "Y_DIR") (class "Default")
      (node (ref "J4") (pin "P$5") (pinfunction "P$5_P$5") (pintype "bidirectional"))
      (node (ref "U5") (pin "115") (pinfunction "P6_7_115") (pintype "bidirectional"))
    )
    (net (code "61") (name "Y_LS") (class "Default")
      (node (ref "J4") (pin "P$4") (pinfunction "P$4_P$4") (pintype "bidirectional"))
      (node (ref "U5") (pin "175") (pinfunction "P5_12_175") (pintype "bidirectional"))
    )
    (net (code "62") (name "Y_STEP") (class "Default")
      (node (ref "J4") (pin "P$13") (pinfunction "P$13_P$13") (pintype "bidirectional"))
      (node (ref "U5") (pin "82") (pinfunction "P3_4_82") (pintype "bidirectional"))
    )
    (net (code "63") (name "Z_DIR") (class "Default")
      (node (ref "J4") (pin "P$1") (pinfunction "P$1_P$1") (pintype "bidirectional"))
      (node (ref "U5") (pin "121") (pinfunction "P6_1_121") (pintype "bidirectional"))
    )
    (net (code "64") (name "Z_LS") (class "Default")
      (node (ref "J4") (pin "P$6") (pinfunction "P$6_P$6") (pintype "bidirectional"))
      (node (ref "U5") (pin "169") (pinfunction "P0_0/AN0\\00_169") (pintype "bidirectional"))
    )
    (net (code "65") (name "Z_STEP") (class "Default")
      (node (ref "J4") (pin "P$9") (pinfunction "P$9_P$9") (pintype "bidirectional"))
      (node (ref "U5") (pin "92") (pinfunction "P1_11_92") (pintype "bidirectional"))
    )
    (net (code "66") (name "unconnected-(U5-P0_1{slash}AN001-Pad168)") (class "Default")
      (node (ref "U5") (pin "168") (pinfunction "P0_1/AN001_168") (pintype "bidirectional"))
    )
    (net (code "67") (name "unconnected-(U5-P0_2{slash}AN002-Pad167)") (class "Default")
      (node (ref "U5") (pin "167") (pinfunction "P0_2/AN002_167") (pintype "bidirectional"))
    )
    (net (code "68") (name "unconnected-(U5-P0_3{slash}PGAVSS000-Pad166)") (class "Default")
      (node (ref "U5") (pin "166") (pinfunction "P0_3/PGAVSS000_166") (pintype "bidirectional"))
    )
    (net (code "69") (name "unconnected-(U5-P0_4{slash}AN100-Pad165)") (class "Default")
      (node (ref "U5") (pin "165") (pinfunction "P0_4/AN100_165") (pintype "bidirectional"))
    )
    (net (code "70") (name "unconnected-(U5-P0_6{slash}AN102-Pad163)") (class "Default")
      (node (ref "U5") (pin "163") (pinfunction "P0_6/AN102_163") (pintype "bidirectional"))
    )
    (net (code "71") (name "unconnected-(U5-P0_7{slash}PGVSS100-Pad162)") (class "Default")
      (node (ref "U5") (pin "162") (pinfunction "P0_7/PGVSS100_162") (pintype "bidirectional"))
    )
    (net (code "72") (name "unconnected-(U5-P0_8{slash}AN003-Pad161)") (class "Default")
      (node (ref "U5") (pin "161") (pinfunction "P0_8/AN003_161") (pintype "bidirectional"))
    )
    (net (code "73") (name "unconnected-(U5-P0_9{slash}AN004-Pad160)") (class "Default")
      (node (ref "U5") (pin "160") (pinfunction "P0_9/AN004_160") (pintype "bidirectional"))
    )
    (net (code "74") (name "unconnected-(U5-P0_14{slash}DA0{slash}AN005{slash}AN105-Pad152)") (class "Default")
      (node (ref "U5") (pin "152") (pinfunction "P0_14/DA0/AN005/AN105_152") (pintype "bidirectional"))
    )
    (net (code "75") (name "unconnected-(U5-P0_15{slash}DA1{slash}AN006{slash}AN106-Pad151)") (class "Default")
      (node (ref "U5") (pin "151") (pinfunction "P0_15/DA1/AN006/AN106_151") (pintype "bidirectional"))
    )
    (net (code "76") (name "unconnected-(U5-P1_0-Pad132)") (class "Default")
      (node (ref "U5") (pin "132") (pinfunction "P1_0_132") (pintype "bidirectional"))
    )
    (net (code "77") (name "unconnected-(U5-P1_1-Pad131)") (class "Default")
      (node (ref "U5") (pin "131") (pinfunction "P1_1_131") (pintype "bidirectional"))
    )
    (net (code "78") (name "unconnected-(U5-P1_2-Pad130)") (class "Default")
      (node (ref "U5") (pin "130") (pinfunction "P1_2_130") (pintype "bidirectional"))
    )
    (net (code "79") (name "unconnected-(U5-P1_3-Pad129)") (class "Default")
      (node (ref "U5") (pin "129") (pinfunction "P1_3_129") (pintype "bidirectional"))
    )
    (net (code "80") (name "unconnected-(U5-P1_4-Pad128)") (class "Default")
      (node (ref "U5") (pin "128") (pinfunction "P1_4_128") (pintype "bidirectional"))
    )
    (net (code "81") (name "unconnected-(U5-P1_5-Pad127)") (class "Default")
      (node (ref "U5") (pin "127") (pinfunction "P1_5_127") (pintype "bidirectional"))
    )
    (net (code "82") (name "unconnected-(U5-P1_6-Pad126)") (class "Default")
      (node (ref "U5") (pin "126") (pinfunction "P1_6_126") (pintype "bidirectional"))
    )
    (net (code "83") (name "unconnected-(U5-P1_7-Pad125)") (class "Default")
      (node (ref "U5") (pin "125") (pinfunction "P1_7_125") (pintype "bidirectional"))
    )
    (net (code "84") (name "unconnected-(U5-P1_12-Pad93)") (class "Default")
      (node (ref "U5") (pin "93") (pinfunction "P1_12_93") (pintype "bidirectional"))
    )
    (net (code "85") (name "unconnected-(U5-P1_13-Pad94)") (class "Default")
      (node (ref "U5") (pin "94") (pinfunction "P1_13_94") (pintype "bidirectional"))
    )
    (net (code "86") (name "unconnected-(U5-P1_14-Pad95)") (class "Default")
      (node (ref "U5") (pin "95") (pinfunction "P1_14_95") (pintype "bidirectional"))
    )
    (net (code "87") (name "unconnected-(U5-P1_15-Pad96)") (class "Default")
      (node (ref "U5") (pin "96") (pinfunction "P1_15_96") (pintype "bidirectional"))
    )
    (net (code "88") (name "unconnected-(U5-P2_0(INPUT_ONLY)-Pad69)") (class "Default")
      (node (ref "U5") (pin "69") (pinfunction "P2_0(INPUT_ONLY)_69") (pintype "bidirectional"))
    )
    (net (code "89") (name "unconnected-(U5-P2_7-Pad49)") (class "Default")
      (node (ref "U5") (pin "49") (pinfunction "P2_7_49") (pintype "bidirectional"))
    )
    (net (code "90") (name "unconnected-(U5-P3_1-Pad87)") (class "Default")
      (node (ref "U5") (pin "87") (pinfunction "P3_1_87") (pintype "bidirectional"))
    )
    (net (code "91") (name "unconnected-(U5-P3_3-Pad85)") (class "Default")
      (node (ref "U5") (pin "85") (pinfunction "P3_3_85") (pintype "bidirectional"))
    )
    (net (code "92") (name "unconnected-(U5-P3_5-Pad81)") (class "Default")
      (node (ref "U5") (pin "81") (pinfunction "P3_5_81") (pintype "bidirectional"))
    )
    (net (code "93") (name "unconnected-(U5-P3_6-Pad80)") (class "Default")
      (node (ref "U5") (pin "80") (pinfunction "P3_6_80") (pintype "bidirectional"))
    )
    (net (code "94") (name "unconnected-(U5-P3_7-Pad79)") (class "Default")
      (node (ref "U5") (pin "79") (pinfunction "P3_7_79") (pintype "bidirectional"))
    )
    (net (code "95") (name "unconnected-(U5-P3_9-Pad77)") (class "Default")
      (node (ref "U5") (pin "77") (pinfunction "P3_9_77") (pintype "bidirectional"))
    )
    (net (code "96") (name "unconnected-(U5-P3_10-Pad76)") (class "Default")
      (node (ref "U5") (pin "76") (pinfunction "P3_10_76") (pintype "bidirectional"))
    )
    (net (code "97") (name "unconnected-(U5-P3_11-Pad75)") (class "Default")
      (node (ref "U5") (pin "75") (pinfunction "P3_11_75") (pintype "bidirectional"))
    )
    (net (code "98") (name "unconnected-(U5-P3_12-Pad74)") (class "Default")
      (node (ref "U5") (pin "74") (pinfunction "P3_12_74") (pintype "bidirectional"))
    )
    (net (code "99") (name "unconnected-(U5-P3_13-Pad55)") (class "Default")
      (node (ref "U5") (pin "55") (pinfunction "P3_13_55") (pintype "bidirectional"))
    )
    (net (code "100") (name "unconnected-(U5-P3_14-Pad56)") (class "Default")
      (node (ref "U5") (pin "56") (pinfunction "P3_14_56") (pintype "bidirectional"))
    )
    (net (code "101") (name "unconnected-(U5-P3_15-Pad57)") (class "Default")
      (node (ref "U5") (pin "57") (pinfunction "P3_15_57") (pintype "bidirectional"))
    )
    (net (code "102") (name "unconnected-(U5-P4_0-Pad1)") (class "Default")
      (node (ref "U5") (pin "1") (pinfunction "P4_0_1") (pintype "bidirectional"))
    )
    (net (code "103") (name "unconnected-(U5-P4_1-Pad2)") (class "Default")
      (node (ref "U5") (pin "2") (pinfunction "P4_1_2") (pintype "bidirectional"))
    )
    (net (code "104") (name "unconnected-(U5-P4_2-Pad3)") (class "Default")
      (node (ref "U5") (pin "3") (pinfunction "P4_2_3") (pintype "bidirectional"))
    )
    (net (code "105") (name "unconnected-(U5-P4_8-Pad43)") (class "Default")
      (node (ref "U5") (pin "43") (pinfunction "P4_8_43") (pintype "bidirectional"))
    )
    (net (code "106") (name "unconnected-(U5-P4_10-Pad41)") (class "Default")
      (node (ref "U5") (pin "41") (pinfunction "P4_10_41") (pintype "bidirectional"))
    )
    (net (code "107") (name "unconnected-(U5-P4_11-Pad40)") (class "Default")
      (node (ref "U5") (pin "40") (pinfunction "P4_11_40") (pintype "bidirectional"))
    )
    (net (code "108") (name "unconnected-(U5-P4_12-Pad39)") (class "Default")
      (node (ref "U5") (pin "39") (pinfunction "P4_12_39") (pintype "bidirectional"))
    )
    (net (code "109") (name "unconnected-(U5-P4_13-Pad38)") (class "Default")
      (node (ref "U5") (pin "38") (pinfunction "P4_13_38") (pintype "bidirectional"))
    )
    (net (code "110") (name "unconnected-(U5-P4_14-Pad37)") (class "Default")
      (node (ref "U5") (pin "37") (pinfunction "P4_14_37") (pintype "bidirectional"))
    )
    (net (code "111") (name "unconnected-(U5-P4_15-Pad36)") (class "Default")
      (node (ref "U5") (pin "36") (pinfunction "P4_15_36") (pintype "bidirectional"))
    )
    (net (code "112") (name "unconnected-(U5-P5_0{slash}AN016-Pad140)") (class "Default")
      (node (ref "U5") (pin "140") (pinfunction "P5_0/AN016_140") (pintype "bidirectional"))
    )
    (net (code "113") (name "unconnected-(U5-P5_1{slash}AN116-Pad141)") (class "Default")
      (node (ref "U5") (pin "141") (pinfunction "P5_1/AN116_141") (pintype "bidirectional"))
    )
    (net (code "114") (name "unconnected-(U5-P5_2{slash}AN017-Pad142)") (class "Default")
      (node (ref "U5") (pin "142") (pinfunction "P5_2/AN017_142") (pintype "bidirectional"))
    )
    (net (code "115") (name "unconnected-(U5-P5_3{slash}AN117-Pad143)") (class "Default")
      (node (ref "U5") (pin "143") (pinfunction "P5_3/AN117_143") (pintype "bidirectional"))
    )
    (net (code "116") (name "unconnected-(U5-P5_4{slash}AN018-Pad144)") (class "Default")
      (node (ref "U5") (pin "144") (pinfunction "P5_4/AN018_144") (pintype "bidirectional"))
    )
    (net (code "117") (name "unconnected-(U5-P5_5{slash}AN118-Pad145)") (class "Default")
      (node (ref "U5") (pin "145") (pinfunction "P5_5/AN118_145") (pintype "bidirectional"))
    )
    (net (code "118") (name "unconnected-(U5-P5_6{slash}AN019-Pad146)") (class "Default")
      (node (ref "U5") (pin "146") (pinfunction "P5_6/AN019_146") (pintype "bidirectional"))
    )
    (net (code "119") (name "unconnected-(U5-P5_7{slash}AN119-Pad147)") (class "Default")
      (node (ref "U5") (pin "147") (pinfunction "P5_7/AN119_147") (pintype "bidirectional"))
    )
    (net (code "120") (name "unconnected-(U5-P5_11-Pad176)") (class "Default")
      (node (ref "U5") (pin "176") (pinfunction "P5_11_176") (pintype "bidirectional"))
    )
    (net (code "121") (name "unconnected-(U5-P5_13-Pad174)") (class "Default")
      (node (ref "U5") (pin "174") (pinfunction "P5_13_174") (pintype "bidirectional"))
    )
    (net (code "122") (name "unconnected-(U5-P6_0-Pad122)") (class "Default")
      (node (ref "U5") (pin "122") (pinfunction "P6_0_122") (pintype "bidirectional"))
    )
    (net (code "123") (name "unconnected-(U5-P6_2-Pad120)") (class "Default")
      (node (ref "U5") (pin "120") (pinfunction "P6_2_120") (pintype "bidirectional"))
    )
    (net (code "124") (name "unconnected-(U5-P6_3-Pad119)") (class "Default")
      (node (ref "U5") (pin "119") (pinfunction "P6_3_119") (pintype "bidirectional"))
    )
    (net (code "125") (name "unconnected-(U5-P6_5-Pad117)") (class "Default")
      (node (ref "U5") (pin "117") (pinfunction "P6_5_117") (pintype "bidirectional"))
    )
    (net (code "126") (name "unconnected-(U5-P6_6-Pad116)") (class "Default")
      (node (ref "U5") (pin "116") (pinfunction "P6_6_116") (pintype "bidirectional"))
    )
    (net (code "127") (name "unconnected-(U5-P6_8-Pad99)") (class "Default")
      (node (ref "U5") (pin "99") (pinfunction "P6_8_99") (pintype "bidirectional"))
    )
    (net (code "128") (name "unconnected-(U5-P6_9-Pad100)") (class "Default")
      (node (ref "U5") (pin "100") (pinfunction "P6_9_100") (pintype "bidirectional"))
    )
    (net (code "129") (name "unconnected-(U5-P6_11-Pad102)") (class "Default")
      (node (ref "U5") (pin "102") (pinfunction "P6_11_102") (pintype "bidirectional"))
    )
    (net (code "130") (name "unconnected-(U5-P6_12-Pad103)") (class "Default")
      (node (ref "U5") (pin "103") (pinfunction "P6_12_103") (pintype "bidirectional"))
    )
    (net (code "131") (name "unconnected-(U5-P6_13-Pad104)") (class "Default")
      (node (ref "U5") (pin "104") (pinfunction "P6_13_104") (pintype "bidirectional"))
    )
    (net (code "132") (name "unconnected-(U5-P6_14-Pad105)") (class "Default")
      (node (ref "U5") (pin "105") (pinfunction "P6_14_105") (pintype "bidirectional"))
    )
    (net (code "133") (name "unconnected-(U5-P6_15-Pad106)") (class "Default")
      (node (ref "U5") (pin "106") (pinfunction "P6_15_106") (pintype "bidirectional"))
    )
    (net (code "134") (name "unconnected-(U5-P7_6-Pad14)") (class "Default")
      (node (ref "U5") (pin "14") (pinfunction "P7_6_14") (pintype "bidirectional"))
    )
    (net (code "135") (name "unconnected-(U5-P7_7-Pad15)") (class "Default")
      (node (ref "U5") (pin "15") (pinfunction "P7_7_15") (pintype "bidirectional"))
    )
    (net (code "136") (name "unconnected-(U5-P8_0-Pad133)") (class "Default")
      (node (ref "U5") (pin "133") (pinfunction "P8_0_133") (pintype "bidirectional"))
    )
    (net (code "137") (name "unconnected-(U5-P8_1-Pad134)") (class "Default")
      (node (ref "U5") (pin "134") (pinfunction "P8_1_134") (pintype "bidirectional"))
    )
    (net (code "138") (name "unconnected-(U5-P8_2-Pad135)") (class "Default")
      (node (ref "U5") (pin "135") (pinfunction "P8_2_135") (pintype "bidirectional"))
    )
    (net (code "139") (name "unconnected-(U5-P8_3-Pad136)") (class "Default")
      (node (ref "U5") (pin "136") (pinfunction "P8_3_136") (pintype "bidirectional"))
    )
    (net (code "140") (name "unconnected-(U5-P8_4-Pad137)") (class "Default")
      (node (ref "U5") (pin "137") (pinfunction "P8_4_137") (pintype "bidirectional"))
    )
    (net (code "141") (name "unconnected-(U5-P8_5-Pad173)") (class "Default")
      (node (ref "U5") (pin "173") (pinfunction "P8_5_173") (pintype "bidirectional"))
    )
    (net (code "142") (name "unconnected-(U5-P9_0-Pad58)") (class "Default")
      (node (ref "U5") (pin "58") (pinfunction "P9_0_58") (pintype "bidirectional"))
    )
    (net (code "143") (name "unconnected-(U5-P9_1-Pad59)") (class "Default")
      (node (ref "U5") (pin "59") (pinfunction "P9_1_59") (pintype "bidirectional"))
    )
    (net (code "144") (name "unconnected-(U5-P9_5-Pad73)") (class "Default")
      (node (ref "U5") (pin "73") (pinfunction "P9_5_73") (pintype "bidirectional"))
    )
    (net (code "145") (name "unconnected-(U5-P9_6-Pad72)") (class "Default")
      (node (ref "U5") (pin "72") (pinfunction "P9_6_72") (pintype "bidirectional"))
    )
    (net (code "146") (name "unconnected-(U5-P9_7-Pad71)") (class "Default")
      (node (ref "U5") (pin "71") (pinfunction "P9_7_71") (pintype "bidirectional"))
    )
    (net (code "147") (name "unconnected-(U5-P9_8-Pad70)") (class "Default")
      (node (ref "U5") (pin "70") (pinfunction "P9_8_70") (pintype "bidirectional"))
    )
    (net (code "148") (name "unconnected-(U5-PA_0-Pad114)") (class "Default")
      (node (ref "U5") (pin "114") (pinfunction "PA_0_114") (pintype "bidirectional"))
    )
    (net (code "149") (name "unconnected-(U5-PA_1-Pad113)") (class "Default")
      (node (ref "U5") (pin "113") (pinfunction "PA_1_113") (pintype "bidirectional"))
    )
    (net (code "150") (name "unconnected-(U5-PA_8-Pad107)") (class "Default")
      (node (ref "U5") (pin "107") (pinfunction "PA_8_107") (pintype "bidirectional"))
    )
    (net (code "151") (name "unconnected-(U5-PA_9-Pad108)") (class "Default")
      (node (ref "U5") (pin "108") (pinfunction "PA_9_108") (pintype "bidirectional"))
    )
    (net (code "152") (name "unconnected-(U5-PA_10-Pad109)") (class "Default")
      (node (ref "U5") (pin "109") (pinfunction "PA_10_109") (pintype "bidirectional"))
    )
    (net (code "153") (name "unconnected-(U5-VBAT-Pad18)") (class "Default")
      (node (ref "U5") (pin "18") (pinfunction "VBAT_18") (pintype "bidirectional"))
    )
    (net (code "154") (name "unconnected-(U5-VREFH-Pad154)") (class "Default")
      (node (ref "U5") (pin "154") (pinfunction "VREFH_154") (pintype "bidirectional"))
    )
    (net (code "155") (name "unconnected-(U5-VREFH0-Pad158)") (class "Default")
      (node (ref "U5") (pin "158") (pinfunction "VREFH0_158") (pintype "bidirectional"))
    )
    (net (code "156") (name "unconnected-(U5-VREFL-Pad153)") (class "Default")
      (node (ref "U5") (pin "153") (pinfunction "VREFL_153") (pintype "bidirectional"))
    )
    (net (code "157") (name "unconnected-(U5-VREFL0-Pad157)") (class "Default")
      (node (ref "U5") (pin "157") (pinfunction "VREFL0_157") (pintype "bidirectional"))
    )
  )
)
